# FrequencyProbe.net
KiCad netlist of a schematic drawn in EAGLE
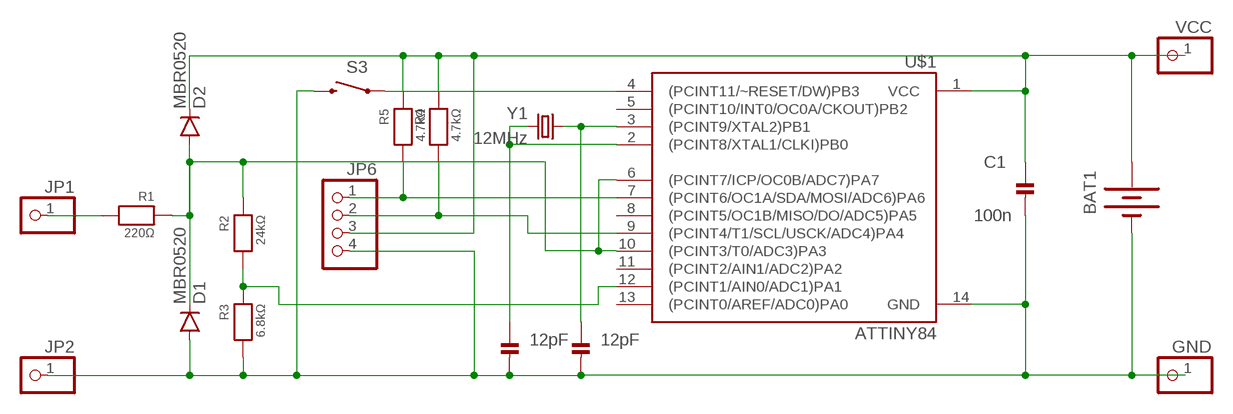
[diagram p0: schematic, sheet 1]

(export (version "E")
  (design (tool "Eeschema 10.0.6"))
  (components
    (comp (ref "BAT1")
      (value "BATTERY12MM")
      (footprint "eagle-import:BATTCON_12MM")
      (libsource (lib "eagle-import") (part "BATTERY12MM"))
    )
    (comp (ref "C1")
      (value "100n")
      (footprint "eagle-import:_0805MP")
      (libsource (lib "eagle-import") (part "CAP_CERAMIC_0805MP"))
    )
    (comp (ref "C12")
      (value "12pF")
      (footprint "eagle-import:_0805MP")
      (libsource (lib "eagle-import") (part "CAP_CERAMIC_0805MP"))
    )
    (comp (ref "C13")
      (value "12pF")
      (footprint "eagle-import:_0805MP")
      (libsource (lib "eagle-import") (part "CAP_CERAMIC_0805MP"))
    )
    (comp (ref "D1")
      (value "MBR0520")
      (footprint "eagle-import:SOD-123")
      (libsource (lib "eagle-import") (part "DIODESOD123"))
    )
    (comp (ref "D2")
      (value "MBR0520")
      (footprint "eagle-import:SOD-123")
      (libsource (lib "eagle-import") (part "DIODESOD123"))
    )
    (comp (ref "GND")
      (value "PINHD-1X1CB")
      (footprint "eagle-import:1X01-CLEANBIG")
      (libsource (lib "eagle-import") (part "PINHD-1X1CB"))
    )
    (comp (ref "JP1")
      (value "PINHD-1X1CB")
      (footprint "eagle-import:1X01-CLEANBIG")
      (libsource (lib "eagle-import") (part "PINHD-1X1CB"))
    )
    (comp (ref "JP2")
      (value "PINHD-1X1CB")
      (footprint "eagle-import:1X01-CLEANBIG")
      (libsource (lib "eagle-import") (part "PINHD-1X1CB"))
    )
    (comp (ref "JP6")
      (value "HEADER-1X4ROUND")
      (footprint "eagle-import:1X04_ROUND")
      (libsource (lib "eagle-import") (part "HEADER-1X4ROUND"))
    )
    (comp (ref "R1")
      (value "220Ω")
      (footprint "eagle-import:_0805MP")
      (libsource (lib "eagle-import") (part "RESISTOR_0805MP"))
    )
    (comp (ref "R2")
      (value "24kΩ")
      (footprint "eagle-import:_0805MP")
      (libsource (lib "eagle-import") (part "RESISTOR_0805MP"))
    )
    (comp (ref "R3")
      (value "6.8kΩ")
      (footprint "eagle-import:_0805MP")
      (libsource (lib "eagle-import") (part "RESISTOR_0805MP"))
    )
    (comp (ref "R4")
      (value "4.7kΩ")
      (footprint "eagle-import:_0805MP")
      (libsource (lib "eagle-import") (part "RESISTOR_0805MP"))
    )
    (comp (ref "R5")
      (value "4.7kΩ")
      (footprint "eagle-import:_0805MP")
      (libsource (lib "eagle-import") (part "RESISTOR_0805MP"))
    )
    (comp (ref "S3")
      (value "SWITCH-MOMENTARY-2SMD")
      (footprint "eagle-import:TACTILE-SWITCH-SMD")
      (libsource (lib "eagle-import") (part "SWITCH-MOMENTARY-2SMD"))
    )
    (comp (ref "U$1")
      (value "ATTINY84")
      (footprint "eagle-import:SO14")
      (libsource (lib "eagle-import") (part "ATTINY84"))
    )
    (comp (ref "VCC")
      (value "PINHD-1X1CB")
      (footprint "eagle-import:1X01-CLEANBIG")
      (libsource (lib "eagle-import") (part "PINHD-1X1CB"))
    )
    (comp (ref "Y1")
      (value "12MHz")
      (footprint "eagle-import:CRYSTAL-SMD-5X3")
      (libsource (lib "eagle-import") (part "CRYSTALCRYSTAL-SMD-5X3-12MHZ"))
    )
  )
  (nets
    (net (code "1") (name "Net-(BAT1-+)") (class "Default")
      (node (ref "BAT1") (pin "PWR@1") (pinfunction "+_PWR@1") (pintype "power_in"))
      (node (ref "C1") (pin "1") (pinfunction "P$1_1") (pintype "passive"))
      (node (ref "D2") (pin "C") (pinfunction "C_C") (pintype "passive"))
      (node (ref "JP6") (pin "3") (pinfunction "3_3") (pintype "passive"))
      (node (ref "R4") (pin "1") (pinfunction "1_1") (pintype "passive"))
      (node (ref "R5") (pin "1") (pinfunction "1_1") (pintype "passive"))
      (node (ref "U$1") (pin "1") (pinfunction "VCC_1") (pintype "bidirectional"))
      (node (ref "VCC") (pin "1") (pinfunction "1_1") (pintype "passive"))
    )
    (net (code "2") (name "Net-(BAT1--)") (class "Default")
      (node (ref "BAT1") (pin "GND") (pinfunction "-_GND") (pintype "power_in"))
      (node (ref "C1") (pin "2") (pinfunction "P$2_2") (pintype "passive"))
      (node (ref "C12") (pin "2") (pinfunction "P$2_2") (pintype "passive"))
      (node (ref "C13") (pin "2") (pinfunction "P$2_2") (pintype "passive"))
      (node (ref "D1") (pin "A") (pinfunction "A_A") (pintype "passive"))
      (node (ref "GND") (pin "1") (pinfunction "1_1") (pintype "passive"))
      (node (ref "JP2") (pin "1") (pinfunction "1_1") (pintype "passive"))
      (node (ref "JP6") (pin "4") (pinfunction "4_4") (pintype "passive"))
      (node (ref "R3") (pin "2") (pinfunction "2_2") (pintype "passive"))
      (node (ref "S3") (pin "3") (pinfunction "2_3") (pintype "passive"))
      (node (ref "U$1") (pin "14") (pinfunction "GND_14") (pintype "bidirectional"))
    )
    (net (code "3") (name "Net-(C12-P$1)") (class "Default")
      (node (ref "C12") (pin "1") (pinfunction "P$1_1") (pintype "passive"))
      (node (ref "U$1") (pin "3") (pinfunction "(PCINT9/XTAL2)PB1_3") (pintype "bidirectional"))
      (node (ref "Y1") (pin "1") (pinfunction "1_1") (pintype "passive"))
    )
    (net (code "4") (name "Net-(C13-P$1)") (class "Default")
      (node (ref "C13") (pin "1") (pinfunction "P$1_1") (pintype "passive"))
      (node (ref "U$1") (pin "2") (pinfunction "(PCINT8/XTAL1/CLKI)PB0_2") (pintype "bidirectional"))
      (node (ref "Y1") (pin "3") (pinfunction "2_3") (pintype "passive"))
    )
    (net (code "5") (name "Net-(JP1-Pad1)") (class "Default")
      (node (ref "JP1") (pin "1") (pinfunction "1_1") (pintype "passive"))
      (node (ref "R1") (pin "2") (pinfunction "2_2") (pintype "passive"))
    )
    (net (code "6") (name "Net-(U$1-(PCINT1{slash}AIN0{slash}ADC1)PA1)") (class "Default")
      (node (ref "R2") (pin "2") (pinfunction "2_2") (pintype "passive"))
      (node (ref "R3") (pin "1") (pinfunction "1_1") (pintype "passive"))
      (node (ref "U$1") (pin "12") (pinfunction "(PCINT1/AIN0/ADC1)PA1_12") (pintype "bidirectional"))
    )
    (net (code "7") (name "Net-(U$1-(PCINT3{slash}T0{slash}ADC3)PA3)") (class "Default")
      (node (ref "D1") (pin "C") (pinfunction "C_C") (pintype "passive"))
      (node (ref "D2") (pin "A") (pinfunction "A_A") (pintype "passive"))
      (node (ref "R1") (pin "1") (pinfunction "1_1") (pintype "passive"))
      (node (ref "R2") (pin "1") (pinfunction "1_1") (pintype "passive"))
      (node (ref "U$1") (pin "10") (pinfunction "(PCINT3/T0/ADC3)PA3_10") (pintype "bidirectional"))
      (node (ref "U$1") (pin "6") (pinfunction "(PCINT7/ICP/OC0B/ADC7)PA7_6") (pintype "bidirectional"))
    )
    (net (code "8") (name "Net-(U$1-(PCINT4{slash}T1{slash}SCL{slash}USCK{slash}ADC4)PA4)") (class "Default")
      (node (ref "JP6") (pin "2") (pinfunction "2_2") (pintype "passive"))
      (node (ref "R4") (pin "2") (pinfunction "2_2") (pintype "passive"))
      (node (ref "U$1") (pin "9") (pinfunction "(PCINT4/T1/SCL/USCK/ADC4)PA4_9") (pintype "bidirectional"))
    )
    (net (code "9") (name "Net-(U$1-(PCINT6{slash}OC1A{slash}SDA{slash}MOSI{slash}ADC6)PA6)") (class "Default")
      (node (ref "JP6") (pin "1") (pinfunction "1_1") (pintype "passive"))
      (node (ref "R5") (pin "2") (pinfunction "2_2") (pintype "passive"))
      (node (ref "U$1") (pin "7") (pinfunction "(PCINT6/OC1A/SDA/MOSI/ADC6)PA6_7") (pintype "bidirectional"))
    )
    (net (code "10") (name "Net-(U$1-(PCINT11{slash}~{RESET{slash}DW})PB3)") (class "Default")
      (node (ref "S3") (pin "1") (pinfunction "1_1") (pintype "passive"))
      (node (ref "U$1") (pin "4") (pinfunction "(PCINT11/~{RESET/DW})PB3_4") (pintype "bidirectional"))
    )
    (net (code "11") (name "unconnected-(U$1-(PCINT0{slash}AREF{slash}ADC0)PA0-Pad13)") (class "Default")
      (node (ref "U$1") (pin "13") (pinfunction "(PCINT0/AREF/ADC0)PA0_13") (pintype "bidirectional"))
    )
    (net (code "12") (name "unconnected-(U$1-(PCINT2{slash}AIN1{slash}ADC2)PA2-Pad11)") (class "Default")
      (node (ref "U$1") (pin "11") (pinfunction "(PCINT2/AIN1/ADC2)PA2_11") (pintype "bidirectional"))
    )
    (net (code "13") (name "unconnected-(U$1-(PCINT5{slash}OC1B{slash}MISO{slash}DO{slash}ADC5)PA5-Pad8)") (class "Default")
      (node (ref "U$1") (pin "8") (pinfunction "(PCINT5/OC1B/MISO/DO/ADC5)PA5_8") (pintype "bidirectional"))
    )
    (net (code "14") (name "unconnected-(U$1-(PCINT10{slash}INT0{slash}OC0A{slash}CKOUT)PB2-Pad5)") (class "Default")
      (node (ref "U$1") (pin "5") (pinfunction "(PCINT10/INT0/OC0A/CKOUT)PB2_5") (pintype "bidirectional"))
    )
  )
)
